# eCog112_Motor.net
KiCad netlist of a schematic drawn in EAGLE
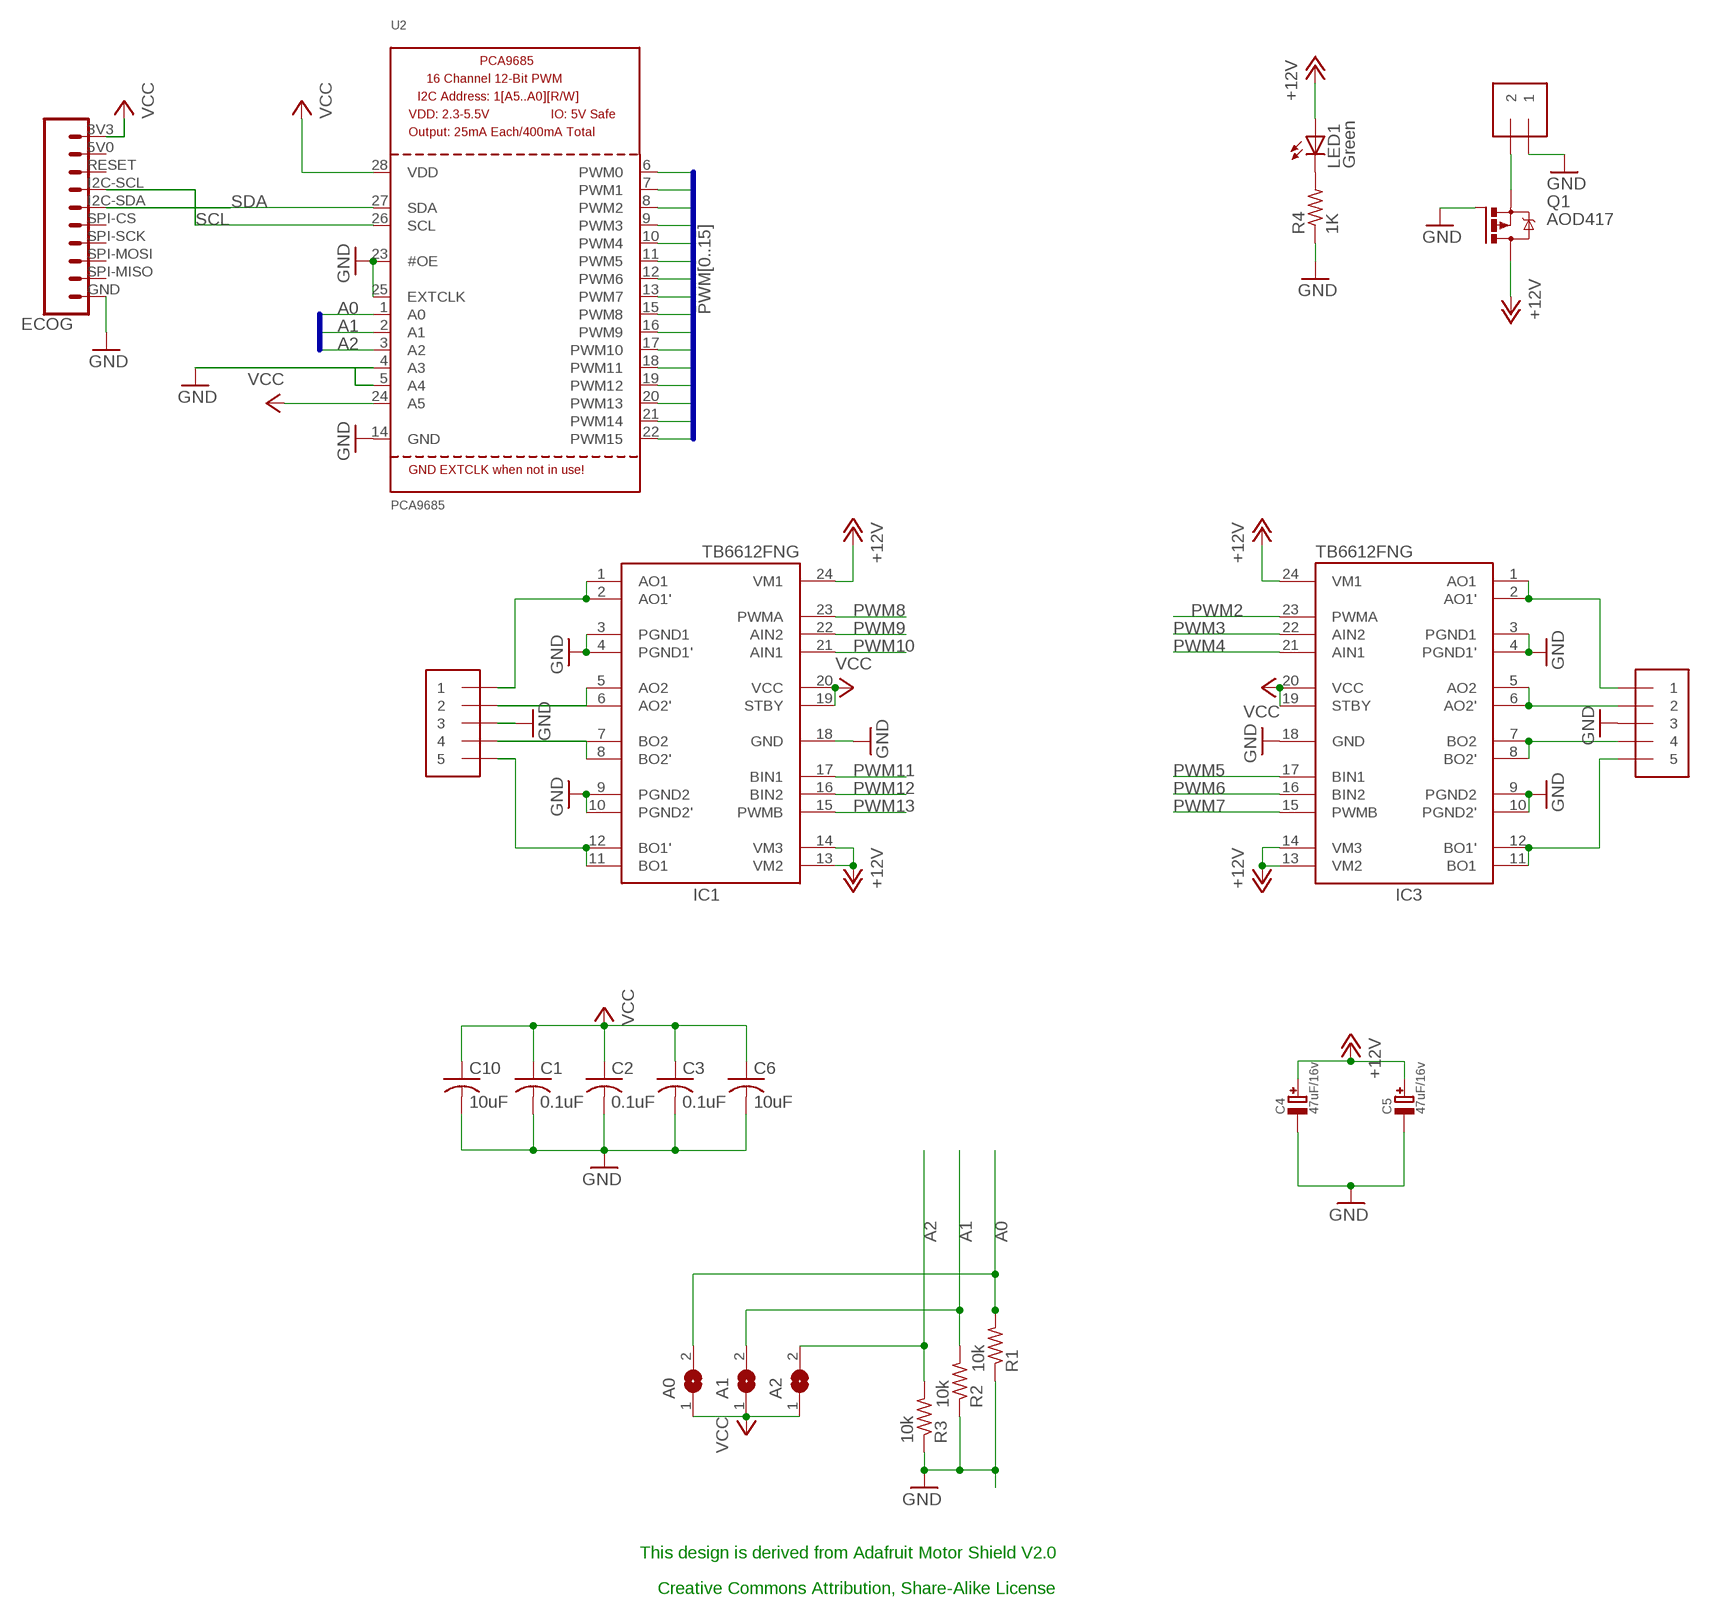
[diagram p0: schematic, sheet 1]

(export (version "E")
  (design (tool "Eeschema 10.0.6"))
  (components
    (comp (ref "A0") (value "SJ") (footprint "eagle-import:SJ") (libsource (lib "eagle-import") (part "SJ")))
    (comp (ref "A1") (value "SJ") (footprint "eagle-import:SJ") (libsource (lib "eagle-import") (part "SJ")))
    (comp (ref "A2") (value "SJ") (footprint "eagle-import:SJ") (libsource (lib "eagle-import") (part "SJ")))
    (comp (ref "C1")
      (value "0.1uF")
      (footprint "eagle-import:C0603")
      (fields
        (field (name "PARTNO") "GRM188F51E104ZA01D,MURATA ELECTRONICS (VA),DK,490-1575-1-ND,CAP CER .1UF 25V Y5V 0603, REF2")
      )
      (libsource (lib "eagle-import") (part "C-USC0603"))
    )
    (comp (ref "C2")
      (value "0.1uF")
      (footprint "eagle-import:C0603")
      (fields
        (field (name "PARTNO") "GRM188F51E104ZA01D,MURATA ELECTRONICS (VA),DK,490-1575-1-ND,CAP CER .1UF 25V Y5V 0603, REF2")
      )
      (libsource (lib "eagle-import") (part "C-USC0603"))
    )
    (comp (ref "C3")
      (value "0.1uF")
      (footprint "eagle-import:C0603")
      (fields
        (field (name "PARTNO") "GRM188F51E104ZA01D,MURATA ELECTRONICS (VA),DK,490-1575-1-ND,CAP CER .1UF 25V Y5V 0603, REF2")
      )
      (libsource (lib "eagle-import") (part "C-USC0603"))
    )
    (comp (ref "C4")
      (value "47uF/16v")
      (footprint "eagle-import:PANASONIC_C")
      (fields
        (field (name "PARTNO") "EEE-1CA470WR,panasonic,dk,PCE3890CT-ND ,CAP ALUM 47UF 20% 16V SMD , REF79")
      )
      (libsource (lib "eagle-import") (part "CAP_ELECTROLYTICPANASONIC_C"))
    )
    (comp (ref "C5")
      (value "47uF/16v")
      (footprint "eagle-import:PANASONIC_C")
      (fields
        (field (name "PARTNO") "EEE-1CA470WR,panasonic,dk,PCE3890CT-ND ,CAP ALUM 47UF 20% 16V SMD , REF79")
      )
      (libsource (lib "eagle-import") (part "CAP_ELECTROLYTICPANASONIC_C"))
    )
    (comp (ref "C6")
      (value "10uF")
      (footprint "eagle-import:C0603")
      (fields
        (field (name "PARTNO") "GRM188R60G106ME47D,MURATA ELECTRONICS (VA),dk,490-3298-1-ND,CAP CER 10UF 4V X5R 0603 , REF83")
      )
      (libsource (lib "eagle-import") (part "C-USC0603"))
    )
    (comp (ref "C10")
      (value "10uF")
      (footprint "eagle-import:C0603")
      (fields
        (field (name "PARTNO") "GRM188R60G106ME47D,MURATA ELECTRONICS (VA),dk,490-3298-1-ND,CAP CER 10UF 4V X5R 0603 , REF83")
      )
      (libsource (lib "eagle-import") (part "C-USC0603"))
    )
    (comp (ref "ECOG")
      (value "ECOG_BUSES_ROWECOG_BUSES_SMD")
      (footprint "eagle-import:ECOG_BUSES_SMD")
      (libsource (lib "eagle-import") (part "ECOG_BUSES_ROWECOG_BUSES_SMD"))
    )
    (comp (ref "IC1")
      (value "TB6612FNG")
      (footprint "eagle-import:SSOP24")
      (fields
        (field (name "PARTNO") "TB6612FNGC8EL,Toshiba,dk,TB6612FNGC8ELCT-ND,IC MOTOR DRIVER PAR 24SSOP , REF80")
      )
      (libsource (lib "eagle-import") (part "TB6612FNG"))
    )
    (comp (ref "IC3")
      (value "TB6612FNG")
      (footprint "eagle-import:SSOP24")
      (fields
        (field (name "PARTNO") "TB6612FNGC8EL,Toshiba,dk,TB6612FNGC8ELCT-ND,IC MOTOR DRIVER PAR 24SSOP , REF80")
      )
      (libsource (lib "eagle-import") (part "TB6612FNG"))
    )
    (comp (ref "J1")
      (value "1X5")
      (footprint "eagle-import:1X05-3.5MM")
      (fields
        (field (name "PARTNO") "1984646,Pheonix Contact,dk,277-1723-ND,CONN TERM BLOCK T/H 5POS 3.5MM , REF84")
      )
      (libsource (lib "eagle-import") (part "1X5"))
    )
    (comp (ref "J2")
      (value "1X5")
      (footprint "eagle-import:1X05-3.5MM")
      (fields
        (field (name "PARTNO") "1984646,Pheonix Contact,dk,277-1723-ND,CONN TERM BLOCK T/H 5POS 3.5MM , REF84")
      )
      (libsource (lib "eagle-import") (part "1X5"))
    )
    (comp (ref "LED1")
      (value "Green")
      (footprint "eagle-import:CHIP-LED0805")
      (fields
        (field (name "PARTNO") "LTST-C170KGKT,LITE-ON INC (VA),DK,160-1414-1-ND,LED GREEN CLEAR 0805 SMD, REF17")
      )
      (libsource (lib "eagle-import") (part "LEDCHIP-LED0805"))
    )
    (comp (ref "MPOWER")
      (value "1X2-3.5MM")
      (footprint "eagle-import:1X2-3.5MM")
      (fields
        (field (name "PARTNO") "1984617,Pheonix Contact,dk,277-1721-ND,CONN TERM BLOCK T/H 2POS 3.5MM , REF85")
      )
      (libsource (lib "eagle-import") (part "1X2-3.5MM"))
    )
    (comp (ref "Q1")
      (value "AOD417")
      (footprint "eagle-import:D-PAK_TO252AA")
      (fields
        (field (name "PARTNO") "AOD417,Alpha & Omega Semiconductor Inc.,dk,785-1106-1-ND,MOSFET P-CH 30V 25A TO252 , REF82")
      )
      (libsource (lib "eagle-import") (part "IRF?5305R"))
    )
    (comp (ref "R1")
      (value "10k")
      (footprint "eagle-import:R0805")
      (fields
        (field (name "PARTNO") "RC0805JR-0710KL,YAGEO (VA),dk,311-10KARCT-ND,RES SMD 10K OHM 5% 1/8W 0805, REF63")
      )
      (libsource (lib "eagle-import") (part "R-US_R0805"))
    )
    (comp (ref "R2")
      (value "10k")
      (footprint "eagle-import:R0805")
      (fields
        (field (name "PARTNO") "RC0805JR-0710KL,YAGEO (VA),dk,311-10KARCT-ND,RES SMD 10K OHM 5% 1/8W 0805, REF63")
      )
      (libsource (lib "eagle-import") (part "R-US_R0805"))
    )
    (comp (ref "R3")
      (value "10k")
      (footprint "eagle-import:R0805")
      (fields
        (field (name "PARTNO") "RC0805JR-0710KL,YAGEO (VA),dk,311-10KARCT-ND,RES SMD 10K OHM 5% 1/8W 0805, REF63")
      )
      (libsource (lib "eagle-import") (part "R-US_R0805"))
    )
    (comp (ref "R4")
      (value "1K")
      (footprint "eagle-import:R0603")
      (fields
        (field (name "PARTNO") "RC0603JR-071KL,YAGEO (VA),dk,311-1.0KGRTR-ND,RES SMD 1K OHM 5% 1/10W 0603 , REF73")
      )
      (libsource (lib "eagle-import") (part "R-US_R0603"))
    )
    (comp (ref "U2")
      (value "PCA9685")
      (footprint "eagle-import:TSSOP28")
      (libsource (lib "eagle-import") (part "PCA9685"))
    )
  )
  (nets
    (net (code "5") (name "+12V") (class "Default")
      (node (ref "C4") (pin "+") (pinfunction "+_+") (pintype "passive"))
      (node (ref "C5") (pin "+") (pinfunction "+_+") (pintype "passive"))
      (node (ref "IC1") (pin "13") (pinfunction "VM2_13") (pintype "power_in"))
      (node (ref "IC1") (pin "14") (pinfunction "VM3_14") (pintype "power_in"))
      (node (ref "IC1") (pin "24") (pinfunction "VM1_24") (pintype "power_in"))
      (node (ref "IC3") (pin "13") (pinfunction "VM2_13") (pintype "power_in"))
      (node (ref "IC3") (pin "14") (pinfunction "VM3_14") (pintype "power_in"))
      (node (ref "IC3") (pin "24") (pinfunction "VM1_24") (pintype "power_in"))
      (node (ref "LED1") (pin "A") (pinfunction "A_A") (pintype "passive"))
      (node (ref "Q1") (pin "4") (pinfunction "D_4") (pintype "passive"))
    )
    (net (code "6") (name "/A0") (class "Default")
      (node (ref "A0") (pin "2") (pinfunction "2_2") (pintype "passive"))
      (node (ref "R1") (pin "2") (pinfunction "2_2") (pintype "passive"))
      (node (ref "U2") (pin "1") (pinfunction "A0_1") (pintype "bidirectional"))
    )
    (net (code "7") (name "/A1") (class "Default")
      (node (ref "A1") (pin "2") (pinfunction "2_2") (pintype "passive"))
      (node (ref "R2") (pin "2") (pinfunction "2_2") (pintype "passive"))
      (node (ref "U2") (pin "2") (pinfunction "A1_2") (pintype "bidirectional"))
    )
    (net (code "8") (name "/A2") (class "Default")
      (node (ref "A2") (pin "2") (pinfunction "2_2") (pintype "passive"))
      (node (ref "R3") (pin "2") (pinfunction "2_2") (pintype "passive"))
      (node (ref "U2") (pin "3") (pinfunction "A2_3") (pintype "bidirectional"))
    )
    (net (code "9") (name "/PWM2") (class "Default")
      (node (ref "IC3") (pin "23") (pinfunction "PWMA_23") (pintype "input"))
      (node (ref "U2") (pin "8") (pinfunction "PWM2_8") (pintype "output"))
    )
    (net (code "10") (name "/PWM3") (class "Default")
      (node (ref "IC3") (pin "22") (pinfunction "AIN2_22") (pintype "input"))
      (node (ref "U2") (pin "9") (pinfunction "PWM3_9") (pintype "output"))
    )
    (net (code "11") (name "/PWM4") (class "Default")
      (node (ref "IC3") (pin "21") (pinfunction "AIN1_21") (pintype "input"))
      (node (ref "U2") (pin "10") (pinfunction "PWM4_10") (pintype "output"))
    )
    (net (code "12") (name "/PWM5") (class "Default")
      (node (ref "IC3") (pin "17") (pinfunction "BIN1_17") (pintype "input"))
      (node (ref "U2") (pin "11") (pinfunction "PWM5_11") (pintype "output"))
    )
    (net (code "13") (name "/PWM6") (class "Default")
      (node (ref "IC3") (pin "16") (pinfunction "BIN2_16") (pintype "input"))
      (node (ref "U2") (pin "12") (pinfunction "PWM6_12") (pintype "output"))
    )
    (net (code "14") (name "/PWM7") (class "Default")
      (node (ref "IC3") (pin "15") (pinfunction "PWMB_15") (pintype "input"))
      (node (ref "U2") (pin "13") (pinfunction "PWM7_13") (pintype "output"))
    )
    (net (code "15") (name "/PWM8") (class "Default")
      (node (ref "IC1") (pin "23") (pinfunction "PWMA_23") (pintype "input"))
      (node (ref "U2") (pin "15") (pinfunction "PWM8_15") (pintype "output"))
    )
    (net (code "16") (name "/PWM9") (class "Default")
      (node (ref "IC1") (pin "22") (pinfunction "AIN2_22") (pintype "input"))
      (node (ref "U2") (pin "16") (pinfunction "PWM9_16") (pintype "output"))
    )
    (net (code "17") (name "/PWM10") (class "Default")
      (node (ref "IC1") (pin "21") (pinfunction "AIN1_21") (pintype "input"))
      (node (ref "U2") (pin "17") (pinfunction "PWM10_17") (pintype "output"))
    )
    (net (code "18") (name "/PWM11") (class "Default")
      (node (ref "IC1") (pin "17") (pinfunction "BIN1_17") (pintype "input"))
      (node (ref "U2") (pin "18") (pinfunction "PWM11_18") (pintype "output"))
    )
    (net (code "19") (name "/PWM12") (class "Default")
      (node (ref "IC1") (pin "16") (pinfunction "BIN2_16") (pintype "input"))
      (node (ref "U2") (pin "19") (pinfunction "PWM12_19") (pintype "output"))
    )
    (net (code "20") (name "/PWM13") (class "Default")
      (node (ref "IC1") (pin "15") (pinfunction "PWMB_15") (pintype "input"))
      (node (ref "U2") (pin "20") (pinfunction "PWM13_20") (pintype "output"))
    )
    (net (code "22") (name "/SCL") (class "Default")
      (node (ref "ECOG") (pin "I2C-SCL") (pinfunction "I2C-SCL_I2C-SCL") (pintype "passive"))
      (node (ref "U2") (pin "26") (pinfunction "SCL_26") (pintype "bidirectional"))
    )
    (net (code "23") (name "/SDA") (class "Default")
      (node (ref "ECOG") (pin "I2C-SDA") (pinfunction "I2C-SDA_I2C-SDA") (pintype "passive"))
      (node (ref "U2") (pin "27") (pinfunction "SDA_27") (pintype "bidirectional"))
    )
    (net (code "24") (name "GND") (class "Default")
      (node (ref "C1") (pin "2") (pinfunction "2_2") (pintype "passive"))
      (node (ref "C10") (pin "2") (pinfunction "2_2") (pintype "passive"))
      (node (ref "C2") (pin "2") (pinfunction "2_2") (pintype "passive"))
      (node (ref "C3") (pin "2") (pinfunction "2_2") (pintype "passive"))
      (node (ref "C4") (pin "-") (pinfunction "-_-") (pintype "passive"))
      (node (ref "C5") (pin "-") (pinfunction "-_-") (pintype "passive"))
      (node (ref "C6") (pin "2") (pinfunction "2_2") (pintype "passive"))
      (node (ref "ECOG") (pin "GND") (pinfunction "GND_GND") (pintype "passive"))
      (node (ref "IC1") (pin "10") (pinfunction "PGND2'_10") (pintype "power_in"))
      (node (ref "IC1") (pin "18") (pinfunction "GND_18") (pintype "power_in"))
      (node (ref "IC1") (pin "3") (pinfunction "PGND1_3") (pintype "power_in"))
      (node (ref "IC1") (pin "4") (pinfunction "PGND1'_4") (pintype "power_in"))
      (node (ref "IC1") (pin "9") (pinfunction "PGND2_9") (pintype "power_in"))
      (node (ref "IC3") (pin "10") (pinfunction "PGND2'_10") (pintype "power_in"))
      (node (ref "IC3") (pin "18") (pinfunction "GND_18") (pintype "power_in"))
      (node (ref "IC3") (pin "3") (pinfunction "PGND1_3") (pintype "power_in"))
      (node (ref "IC3") (pin "4") (pinfunction "PGND1'_4") (pintype "power_in"))
      (node (ref "IC3") (pin "9") (pinfunction "PGND2_9") (pintype "power_in"))
      (node (ref "J1") (pin "3") (pinfunction "3_3") (pintype "passive"))
      (node (ref "J2") (pin "3") (pinfunction "3_3") (pintype "passive"))
      (node (ref "MPOWER") (pin "1") (pinfunction "1_1") (pintype "passive"))
      (node (ref "Q1") (pin "1") (pinfunction "G_1") (pintype "passive"))
      (node (ref "R1") (pin "1") (pinfunction "1_1") (pintype "passive"))
      (node (ref "R2") (pin "1") (pinfunction "1_1") (pintype "passive"))
      (node (ref "R3") (pin "1") (pinfunction "1_1") (pintype "passive"))
      (node (ref "R4") (pin "1") (pinfunction "1_1") (pintype "passive"))
      (node (ref "U2") (pin "14") (pinfunction "GND_14") (pintype "power_in"))
      (node (ref "U2") (pin "23") (pinfunction "#OE_23") (pintype "input"))
      (node (ref "U2") (pin "25") (pinfunction "EXTCLK_25") (pintype "input"))
      (node (ref "U2") (pin "4") (pinfunction "A3_4") (pintype "bidirectional"))
      (node (ref "U2") (pin "5") (pinfunction "A4_5") (pintype "bidirectional"))
    )
    (net (code "25") (name "Net-(IC1-AO1')") (class "Default")
      (node (ref "IC1") (pin "1") (pinfunction "AO1_1") (pintype "output"))
      (node (ref "IC1") (pin "2") (pinfunction "AO1'_2") (pintype "output"))
      (node (ref "J1") (pin "1") (pinfunction "1_1") (pintype "passive"))
    )
    (net (code "26") (name "Net-(IC1-AO2')") (class "Default")
      (node (ref "IC1") (pin "5") (pinfunction "AO2_5") (pintype "output"))
      (node (ref "IC1") (pin "6") (pinfunction "AO2'_6") (pintype "output"))
      (node (ref "J1") (pin "2") (pinfunction "2_2") (pintype "passive"))
    )
    (net (code "27") (name "Net-(IC1-BO1')") (class "Default")
      (node (ref "IC1") (pin "11") (pinfunction "BO1_11") (pintype "output"))
      (node (ref "IC1") (pin "12") (pinfunction "BO1'_12") (pintype "output"))
      (node (ref "J1") (pin "5") (pinfunction "5_5") (pintype "passive"))
    )
    (net (code "28") (name "Net-(IC1-BO2')") (class "Default")
      (node (ref "IC1") (pin "7") (pinfunction "BO2_7") (pintype "output"))
      (node (ref "IC1") (pin "8") (pinfunction "BO2'_8") (pintype "output"))
      (node (ref "J1") (pin "4") (pinfunction "4_4") (pintype "passive"))
    )
    (net (code "29") (name "Net-(IC3-AO1')") (class "Default")
      (node (ref "IC3") (pin "1") (pinfunction "AO1_1") (pintype "output"))
      (node (ref "IC3") (pin "2") (pinfunction "AO1'_2") (pintype "output"))
      (node (ref "J2") (pin "1") (pinfunction "1_1") (pintype "passive"))
    )
    (net (code "30") (name "Net-(IC3-AO2')") (class "Default")
      (node (ref "IC3") (pin "5") (pinfunction "AO2_5") (pintype "output"))
      (node (ref "IC3") (pin "6") (pinfunction "AO2'_6") (pintype "output"))
      (node (ref "J2") (pin "2") (pinfunction "2_2") (pintype "passive"))
    )
    (net (code "31") (name "Net-(IC3-BO1')") (class "Default")
      (node (ref "IC3") (pin "11") (pinfunction "BO1_11") (pintype "output"))
      (node (ref "IC3") (pin "12") (pinfunction "BO1'_12") (pintype "output"))
      (node (ref "J2") (pin "5") (pinfunction "5_5") (pintype "passive"))
    )
    (net (code "32") (name "Net-(IC3-BO2')") (class "Default")
      (node (ref "IC3") (pin "7") (pinfunction "BO2_7") (pintype "output"))
      (node (ref "IC3") (pin "8") (pinfunction "BO2'_8") (pintype "output"))
      (node (ref "J2") (pin "4") (pinfunction "4_4") (pintype "passive"))
    )
    (net (code "33") (name "Net-(LED1-PadC)") (class "Default")
      (node (ref "LED1") (pin "C") (pinfunction "C_C") (pintype "passive"))
      (node (ref "R4") (pin "2") (pinfunction "2_2") (pintype "passive"))
    )
    (net (code "34") (name "Net-(Q1-S)") (class "Default")
      (node (ref "MPOWER") (pin "2") (pinfunction "2_2") (pintype "passive"))
      (node (ref "Q1") (pin "3") (pinfunction "S_3") (pintype "passive"))
    )
    (net (code "35") (name "VCC") (class "Default")
      (node (ref "A0") (pin "1") (pinfunction "1_1") (pintype "passive"))
      (node (ref "A1") (pin "1") (pinfunction "1_1") (pintype "passive"))
      (node (ref "A2") (pin "1") (pinfunction "1_1") (pintype "passive"))
      (node (ref "C1") (pin "1") (pinfunction "1_1") (pintype "passive"))
      (node (ref "C10") (pin "1") (pinfunction "1_1") (pintype "passive"))
      (node (ref "C2") (pin "1") (pinfunction "1_1") (pintype "passive"))
      (node (ref "C3") (pin "1") (pinfunction "1_1") (pintype "passive"))
      (node (ref "C6") (pin "1") (pinfunction "1_1") (pintype "passive"))
      (node (ref "ECOG") (pin "3V3") (pinfunction "3V3_3V3") (pintype "passive"))
      (node (ref "IC1") (pin "19") (pinfunction "STBY_19") (pintype "input"))
      (node (ref "IC1") (pin "20") (pinfunction "VCC_20") (pintype "power_in"))
      (node (ref "IC3") (pin "19") (pinfunction "STBY_19") (pintype "input"))
      (node (ref "IC3") (pin "20") (pinfunction "VCC_20") (pintype "power_in"))
      (node (ref "U2") (pin "24") (pinfunction "A5_24") (pintype "bidirectional"))
      (node (ref "U2") (pin "28") (pinfunction "VDD_28") (pintype "power_in"))
    )
    (net (code "36") (name "unconnected-(ECOG-Pad5V0)") (class "Default")
      (node (ref "ECOG") (pin "5V0") (pinfunction "5V0_5V0") (pintype "passive"))
    )
    (net (code "37") (name "unconnected-(ECOG-PadRESET)") (class "Default")
      (node (ref "ECOG") (pin "RESET") (pinfunction "RESET_RESET") (pintype "passive"))
    )
    (net (code "38") (name "unconnected-(ECOG-PadSPI-CS)") (class "Default")
      (node (ref "ECOG") (pin "SPI-CS") (pinfunction "SPI-CS_SPI-CS") (pintype "passive"))
    )
    (net (code "39") (name "unconnected-(ECOG-PadSPI-MISO)") (class "Default")
      (node (ref "ECOG") (pin "SPI-MISO") (pinfunction "SPI-MISO_SPI-MISO") (pintype "passive"))
    )
    (net (code "40") (name "unconnected-(ECOG-PadSPI-MOSI)") (class "Default")
      (node (ref "ECOG") (pin "SPI-MOSI") (pinfunction "SPI-MOSI_SPI-MOSI") (pintype "passive"))
    )
    (net (code "41") (name "unconnected-(ECOG-PadSPI-SCK)") (class "Default")
      (node (ref "ECOG") (pin "SPI-SCK") (pinfunction "SPI-SCK_SPI-SCK") (pintype "passive"))
    )
    (net (code "42") (name "unconnected-(U2-PWM0-Pad6)") (class "Default")
      (node (ref "U2") (pin "6") (pinfunction "PWM0_6") (pintype "output"))
    )
    (net (code "43") (name "unconnected-(U2-PWM1-Pad7)") (class "Default")
      (node (ref "U2") (pin "7") (pinfunction "PWM1_7") (pintype "output"))
    )
    (net (code "44") (name "unconnected-(U2-PWM14-Pad21)") (class "Default")
      (node (ref "U2") (pin "21") (pinfunction "PWM14_21") (pintype "output"))
    )
    (net (code "45") (name "unconnected-(U2-PWM15-Pad22)") (class "Default")
      (node (ref "U2") (pin "22") (pinfunction "PWM15_22") (pintype "output"))
    )
  )
)
